# M12_ETH_CONN.net
KiCad netlist of a schematic drawn in Altium Designer
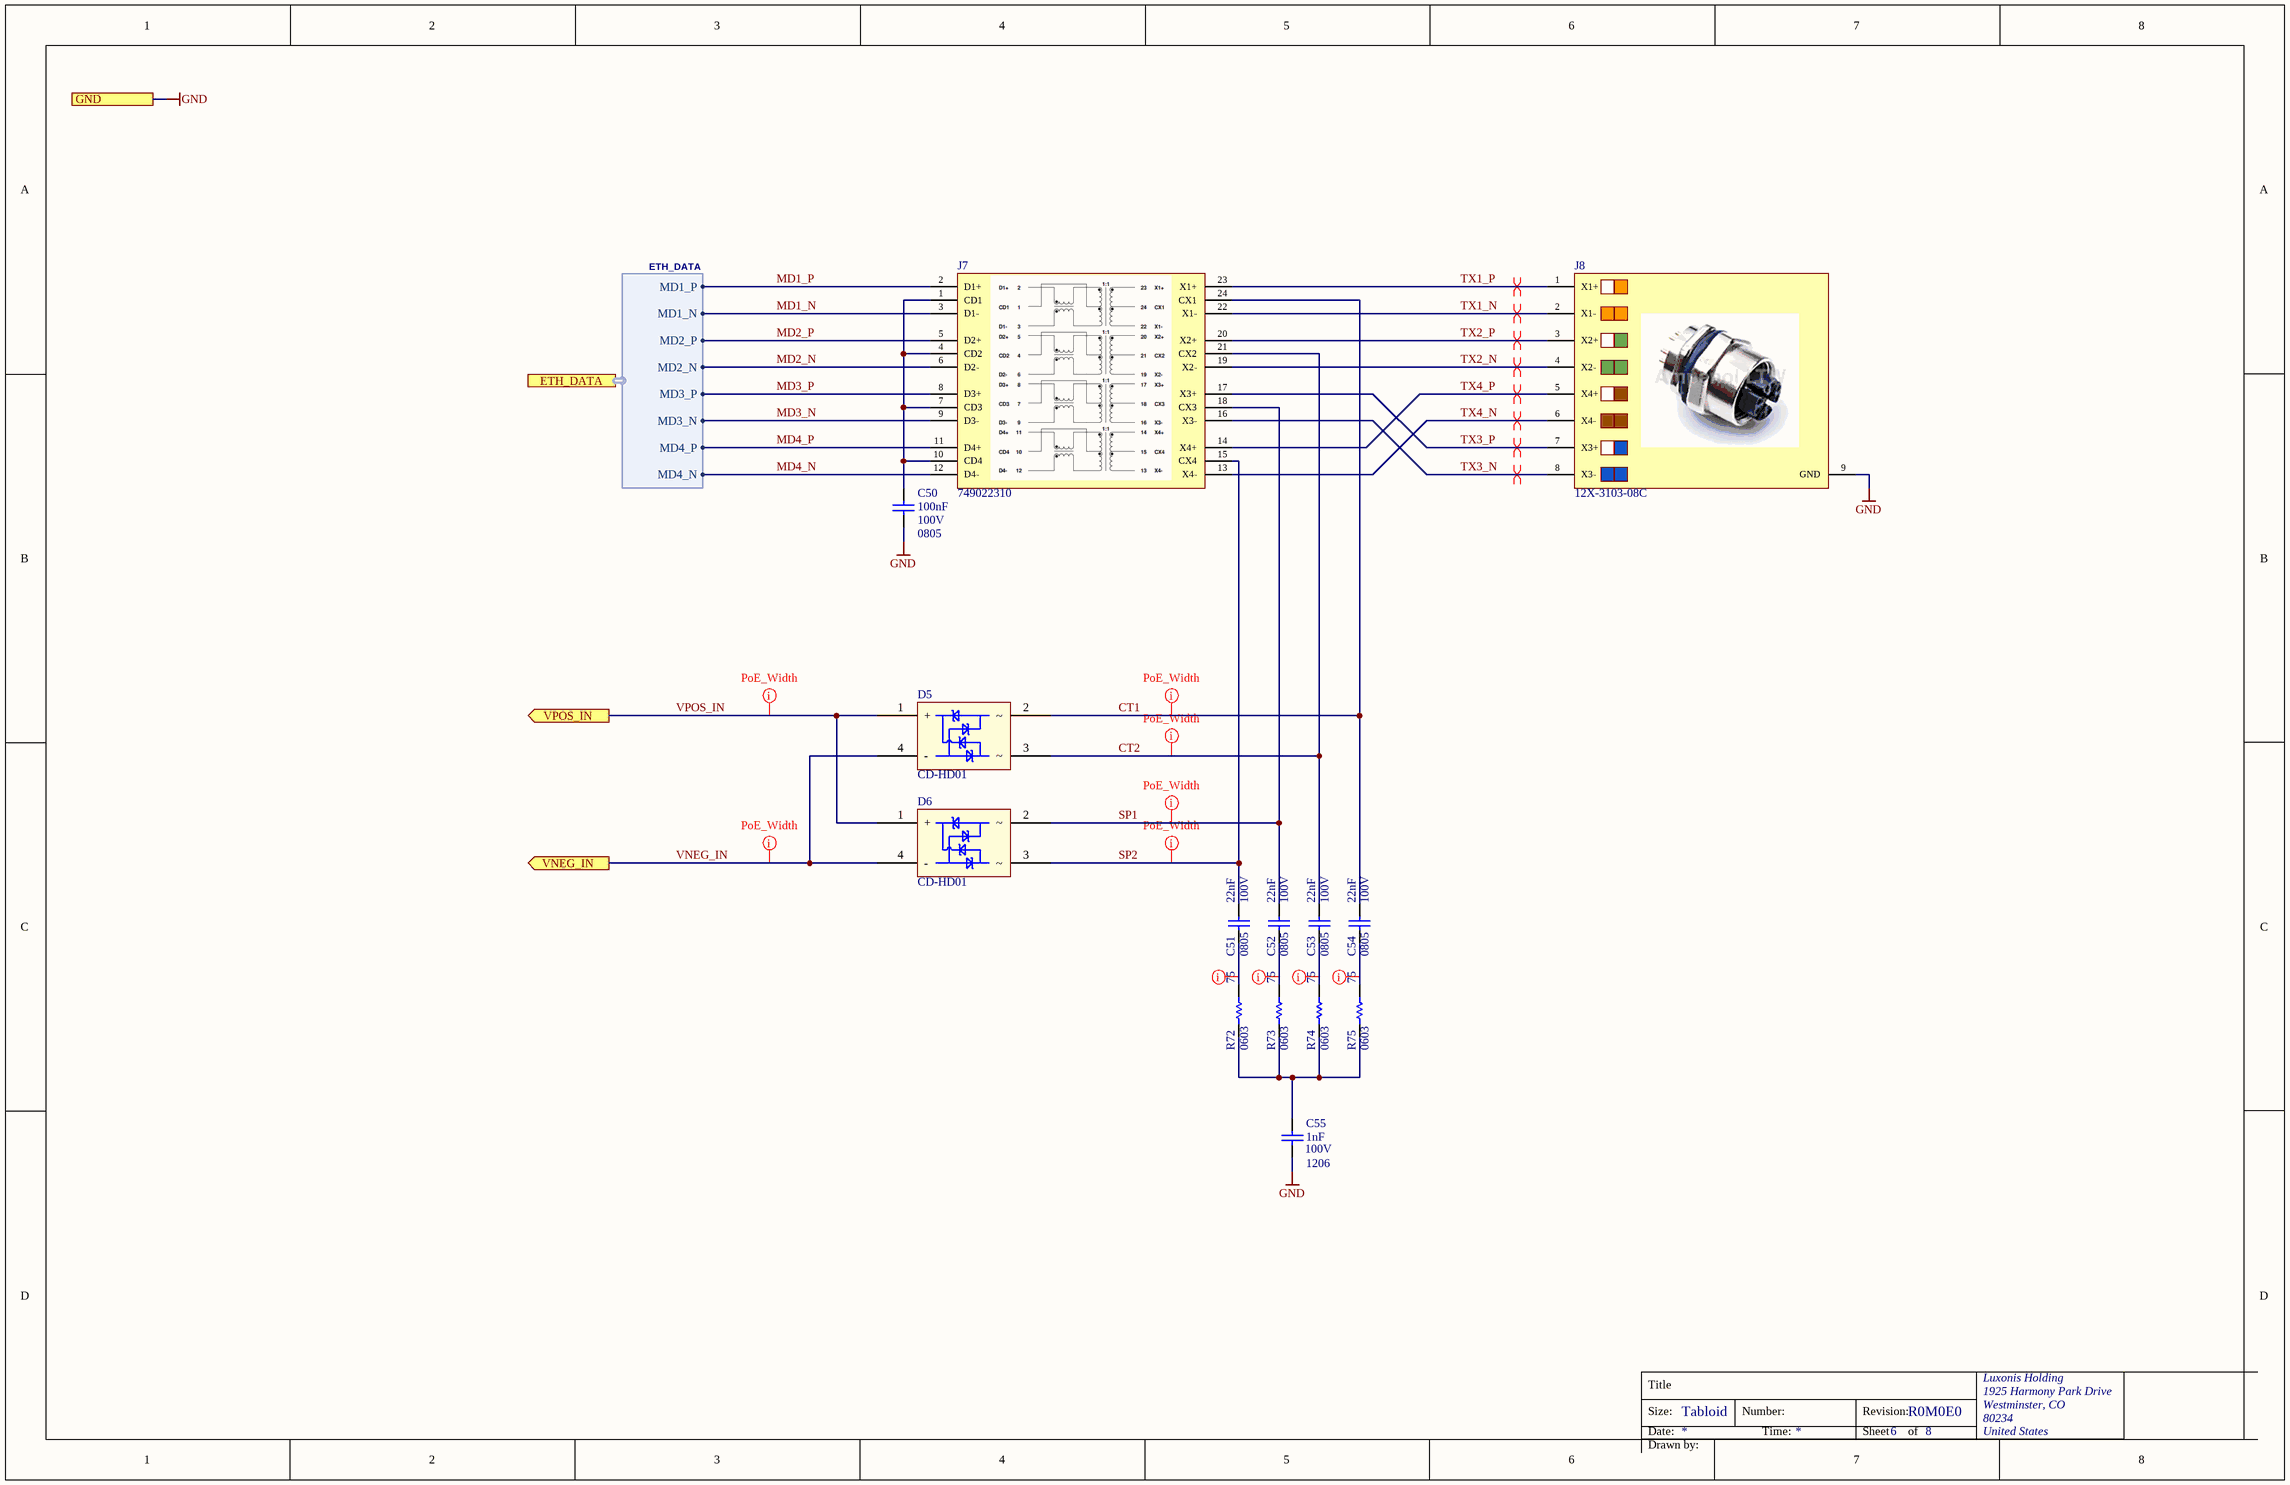
[diagram p0: M12_ETH_CONN.SchDoc]

(export (version "E")
  (design (tool "Eeschema 10.0.6"))
  (components
    (comp (ref "C50")
      (value "100nF")
      (footprint "CAPC0805(2012)145_N")
      (description "CAP CER 0.1UF 100V X7R 0805 10%")
      (fields
        (field (name "VOLTAGE RATING") "100V")
        (field (name "CASE/PACKAGE") "0805")
        (field (name "TOLERANCE") "10%")
        (field (name "Comment") "CL21B104KCFNNNE")
      )
      (libsource (lib "Luxonis LLC") (part "GRM188R61C475KAAJD"))
    )
    (comp (ref "C51")
      (value "22nF")
      (footprint "CAPC0805(2012)145_L")
      (description "CAP CER 22nF 100V X7R 0805 20%")
      (fields
        (field (name "VOLTAGE RATING") "100V")
        (field (name "CASE/PACKAGE") "0805")
        (field (name "TOLERANCE") "20%")
        (field (name "Comment") "C0805C223M1RACAUTO")
      )
      (libsource (lib "Luxonis LLC") (part "LLL153C70G474ME17E"))
    )
    (comp (ref "C52")
      (value "22nF")
      (footprint "CAPC0805(2012)145_L")
      (description "CAP CER 22nF 100V X7R 0805 20%")
      (fields
        (field (name "VOLTAGE RATING") "100V")
        (field (name "CASE/PACKAGE") "0805")
        (field (name "TOLERANCE") "20%")
        (field (name "Comment") "C0805C223M1RACAUTO")
      )
      (libsource (lib "Luxonis LLC") (part "LLL153C70G474ME17E"))
    )
    (comp (ref "C53")
      (value "22nF")
      (footprint "CAPC0805(2012)145_L")
      (description "CAP CER 22nF 100V X7R 0805 20%")
      (fields
        (field (name "VOLTAGE RATING") "100V")
        (field (name "CASE/PACKAGE") "0805")
        (field (name "TOLERANCE") "20%")
        (field (name "Comment") "C0805C223M1RACAUTO")
      )
      (libsource (lib "Luxonis LLC") (part "LLL153C70G474ME17E"))
    )
    (comp (ref "C54")
      (value "22nF")
      (footprint "CAPC0805(2012)145_L")
      (description "CAP CER 22nF 100V X7R 0805 20%")
      (fields
        (field (name "VOLTAGE RATING") "100V")
        (field (name "CASE/PACKAGE") "0805")
        (field (name "TOLERANCE") "20%")
        (field (name "Comment") "C0805C223M1RACAUTO")
      )
      (libsource (lib "Luxonis LLC") (part "LLL153C70G474ME17E"))
    )
    (comp (ref "C55")
      (value "1nF")
      (footprint "CAPC1206(3216)130_L")
      (description "CAP CER 1nF 2000V X7R 1206 10%")
      (fields
        (field (name "VOLTAGE RATING") "100V")
        (field (name "CASE/PACKAGE") "1206")
        (field (name "TOLERANCE") "10%")
        (field (name "Comment") "C1206C102KGRACTU")
      )
      (libsource (lib "Luxonis LLC") (part "LLL153C70G474ME17E"))
    )
    (comp (ref "D5")
      (value "CD-HD01")
      (footprint "CD-H01")
      (description "CD-HD0x Series Schottky Bridge Rectifier Diode 100V 4-Pin Surface Mount T/R")
      (libsource (lib "Luxonis LLC") (part "CD-HD01"))
    )
    (comp (ref "D6")
      (value "CD-HD01")
      (footprint "CD-H01")
      (description "CD-HD0x Series Schottky Bridge Rectifier Diode 100V 4-Pin Surface Mount T/R")
      (libsource (lib "Luxonis LLC") (part "CD-HD01"))
    )
    (comp (ref "J7")
      (value "749022310")
      (footprint "749022310")
      (description "WE-LAN AQ SMT Transformer, 1000 Base-T, PoE+ (up to 720 mA), 150uH")
      (libsource (lib "Luxonis LLC") (part "749022310"))
    )
    (comp (ref "J8")
      (value "12X-3103-08C")
      (footprint "12X-3103-08C")
      (description "Conn M12 Circular F 8 POS Solder ST Thru-Hole 8 Terminal 1 Port")
      (libsource (lib "Luxonis LLC") (part "12X-3103-08C"))
    )
    (comp (ref "R72")
      (value "75")
      (footprint "RESC0603(1608)_N")
      (description "RES SMD 75 OHM 150V 1% 1/10W 0603")
      (fields (field (name "CASE/PACKAGE") "0603") (field (name "Comment") "ERJ-UP3F75R0V"))
      (libsource (lib "Luxonis LLC") (part "Default resistor symbol"))
    )
    (comp (ref "R73")
      (value "75")
      (footprint "RESC0603(1608)_N")
      (description "RES SMD 75 OHM 150V 1% 1/10W 0603")
      (fields (field (name "CASE/PACKAGE") "0603") (field (name "Comment") "ERJ-UP3F75R0V"))
      (libsource (lib "Luxonis LLC") (part "Default resistor symbol"))
    )
    (comp (ref "R74")
      (value "75")
      (footprint "RESC0603(1608)_N")
      (description "RES SMD 75 OHM 150V 1% 1/10W 0603")
      (fields (field (name "CASE/PACKAGE") "0603") (field (name "Comment") "ERJ-UP3F75R0V"))
      (libsource (lib "Luxonis LLC") (part "Default resistor symbol"))
    )
    (comp (ref "R75")
      (value "75")
      (footprint "RESC0603(1608)_N")
      (description "RES SMD 75 OHM 150V 1% 1/10W 0603")
      (fields (field (name "CASE/PACKAGE") "0603") (field (name "Comment") "ERJ-UP3F75R0V"))
      (libsource (lib "Luxonis LLC") (part "Default resistor symbol"))
    )
  )
  (nets
    (net (code "2") (name "/CT1") (class "Default")
      (node (ref "C54") (pin "2") (pinfunction "2_2") (pintype "passive"))
      (node (ref "D5") (pin "2") (pinfunction "~_2") (pintype "passive"))
      (node (ref "J7") (pin "24") (pinfunction "CX1_24") (pintype "passive"))
    )
    (net (code "3") (name "/CT2") (class "Default")
      (node (ref "C53") (pin "2") (pinfunction "2_2") (pintype "passive"))
      (node (ref "D5") (pin "3") (pinfunction "~_3") (pintype "passive"))
      (node (ref "J7") (pin "21") (pinfunction "CX2_21") (pintype "passive"))
    )
    (net (code "4") (name "/MD1_N") (class "Default")
      (node (ref "J7") (pin "3") (pinfunction "D1-_3") (pintype "passive"))
    )
    (net (code "5") (name "/MD1_P") (class "Default")
      (node (ref "J7") (pin "2") (pinfunction "D1+_2") (pintype "passive"))
    )
    (net (code "6") (name "/MD2_N") (class "Default")
      (node (ref "J7") (pin "6") (pinfunction "D2-_6") (pintype "passive"))
    )
    (net (code "7") (name "/MD2_P") (class "Default")
      (node (ref "J7") (pin "5") (pinfunction "D2+_5") (pintype "passive"))
    )
    (net (code "8") (name "/MD3_N") (class "Default")
      (node (ref "J7") (pin "9") (pinfunction "D3-_9") (pintype "passive"))
    )
    (net (code "9") (name "/MD3_P") (class "Default")
      (node (ref "J7") (pin "8") (pinfunction "D3+_8") (pintype "passive"))
    )
    (net (code "10") (name "/MD4_N") (class "Default")
      (node (ref "J7") (pin "12") (pinfunction "D4-_12") (pintype "passive"))
    )
    (net (code "11") (name "/MD4_P") (class "Default")
      (node (ref "J7") (pin "11") (pinfunction "D4+_11") (pintype "passive"))
    )
    (net (code "12") (name "/SP1") (class "Default")
      (node (ref "C52") (pin "2") (pinfunction "2_2") (pintype "passive"))
      (node (ref "D6") (pin "2") (pinfunction "~_2") (pintype "passive"))
      (node (ref "J7") (pin "18") (pinfunction "CX3_18") (pintype "passive"))
    )
    (net (code "13") (name "/SP2") (class "Default")
      (node (ref "C51") (pin "2") (pinfunction "2_2") (pintype "passive"))
      (node (ref "D6") (pin "3") (pinfunction "~_3") (pintype "passive"))
      (node (ref "J7") (pin "15") (pinfunction "CX4_15") (pintype "passive"))
    )
    (net (code "14") (name "/TX1_N") (class "Default")
      (node (ref "J7") (pin "22") (pinfunction "X1-_22") (pintype "passive"))
      (node (ref "J8") (pin "2") (pinfunction "X1-_2") (pintype "passive"))
    )
    (net (code "15") (name "/TX1_P") (class "Default")
      (node (ref "J7") (pin "23") (pinfunction "X1+_23") (pintype "passive"))
      (node (ref "J8") (pin "1") (pinfunction "X1+_1") (pintype "passive"))
    )
    (net (code "16") (name "/TX2_N") (class "Default")
      (node (ref "J7") (pin "19") (pinfunction "X2-_19") (pintype "passive"))
      (node (ref "J8") (pin "4") (pinfunction "X2-_4") (pintype "passive"))
    )
    (net (code "17") (name "/TX2_P") (class "Default")
      (node (ref "J7") (pin "20") (pinfunction "X2+_20") (pintype "passive"))
      (node (ref "J8") (pin "3") (pinfunction "X2+_3") (pintype "passive"))
    )
    (net (code "18") (name "/TX3_N") (class "Default")
      (node (ref "J7") (pin "16") (pinfunction "X3-_16") (pintype "passive"))
      (node (ref "J8") (pin "8") (pinfunction "X3-_8") (pintype "passive"))
    )
    (net (code "19") (name "/TX3_P") (class "Default")
      (node (ref "J7") (pin "17") (pinfunction "X3+_17") (pintype "passive"))
      (node (ref "J8") (pin "7") (pinfunction "X3+_7") (pintype "passive"))
    )
    (net (code "20") (name "/TX4_N") (class "Default")
      (node (ref "J7") (pin "13") (pinfunction "X4-_13") (pintype "passive"))
      (node (ref "J8") (pin "6") (pinfunction "X4-_6") (pintype "passive"))
    )
    (net (code "21") (name "/TX4_P") (class "Default")
      (node (ref "J7") (pin "14") (pinfunction "X4+_14") (pintype "passive"))
      (node (ref "J8") (pin "5") (pinfunction "X4+_5") (pintype "passive"))
    )
    (net (code "22") (name "/VNEG_IN") (class "Default")
      (node (ref "D5") (pin "4") (pinfunction "-_4") (pintype "passive"))
      (node (ref "D6") (pin "4") (pinfunction "-_4") (pintype "passive"))
    )
    (net (code "23") (name "/VPOS_IN") (class "Default")
      (node (ref "D5") (pin "1") (pinfunction "+_1") (pintype "passive"))
      (node (ref "D6") (pin "1") (pinfunction "+_1") (pintype "passive"))
    )
    (net (code "25") (name "GND") (class "Default")
      (node (ref "C50") (pin "1") (pinfunction "1_1") (pintype "passive"))
      (node (ref "C55") (pin "1") (pinfunction "1_1") (pintype "passive"))
      (node (ref "J8") (pin "9") (pinfunction "GND_9") (pintype "passive"))
    )
    (net (code "26") (name "Net-(C51-Pad1)") (class "Default")
      (node (ref "C51") (pin "1") (pinfunction "1_1") (pintype "passive"))
      (node (ref "R72") (pin "2") (pinfunction "2_2") (pintype "passive"))
    )
    (net (code "27") (name "Net-(C52-Pad1)") (class "Default")
      (node (ref "C52") (pin "1") (pinfunction "1_1") (pintype "passive"))
      (node (ref "R73") (pin "2") (pinfunction "2_2") (pintype "passive"))
    )
    (net (code "28") (name "Net-(C53-Pad1)") (class "Default")
      (node (ref "C53") (pin "1") (pinfunction "1_1") (pintype "passive"))
      (node (ref "R74") (pin "2") (pinfunction "2_2") (pintype "passive"))
    )
    (net (code "29") (name "Net-(C54-Pad1)") (class "Default")
      (node (ref "C54") (pin "1") (pinfunction "1_1") (pintype "passive"))
      (node (ref "R75") (pin "2") (pinfunction "2_2") (pintype "passive"))
    )
    (net (code "30") (name "Net-(C55-Pad2)") (class "Default")
      (node (ref "C55") (pin "2") (pinfunction "2_2") (pintype "passive"))
      (node (ref "R72") (pin "1") (pinfunction "1_1") (pintype "passive"))
      (node (ref "R73") (pin "1") (pinfunction "1_1") (pintype "passive"))
      (node (ref "R74") (pin "1") (pinfunction "1_1") (pintype "passive"))
      (node (ref "R75") (pin "1") (pinfunction "1_1") (pintype "passive"))
    )
    (net (code "31") (name "Net-(J7-CD1)") (class "Default")
      (node (ref "C50") (pin "2") (pinfunction "2_2") (pintype "passive"))
      (node (ref "J7") (pin "1") (pinfunction "CD1_1") (pintype "passive"))
      (node (ref "J7") (pin "10") (pinfunction "CD4_10") (pintype "passive"))
      (node (ref "J7") (pin "4") (pinfunction "CD2_4") (pintype "passive"))
      (node (ref "J7") (pin "7") (pinfunction "CD3_7") (pintype "passive"))
    )
  )
)
